# Pure_VCA.net
KiCad netlist of a schematic drawn in EAGLE
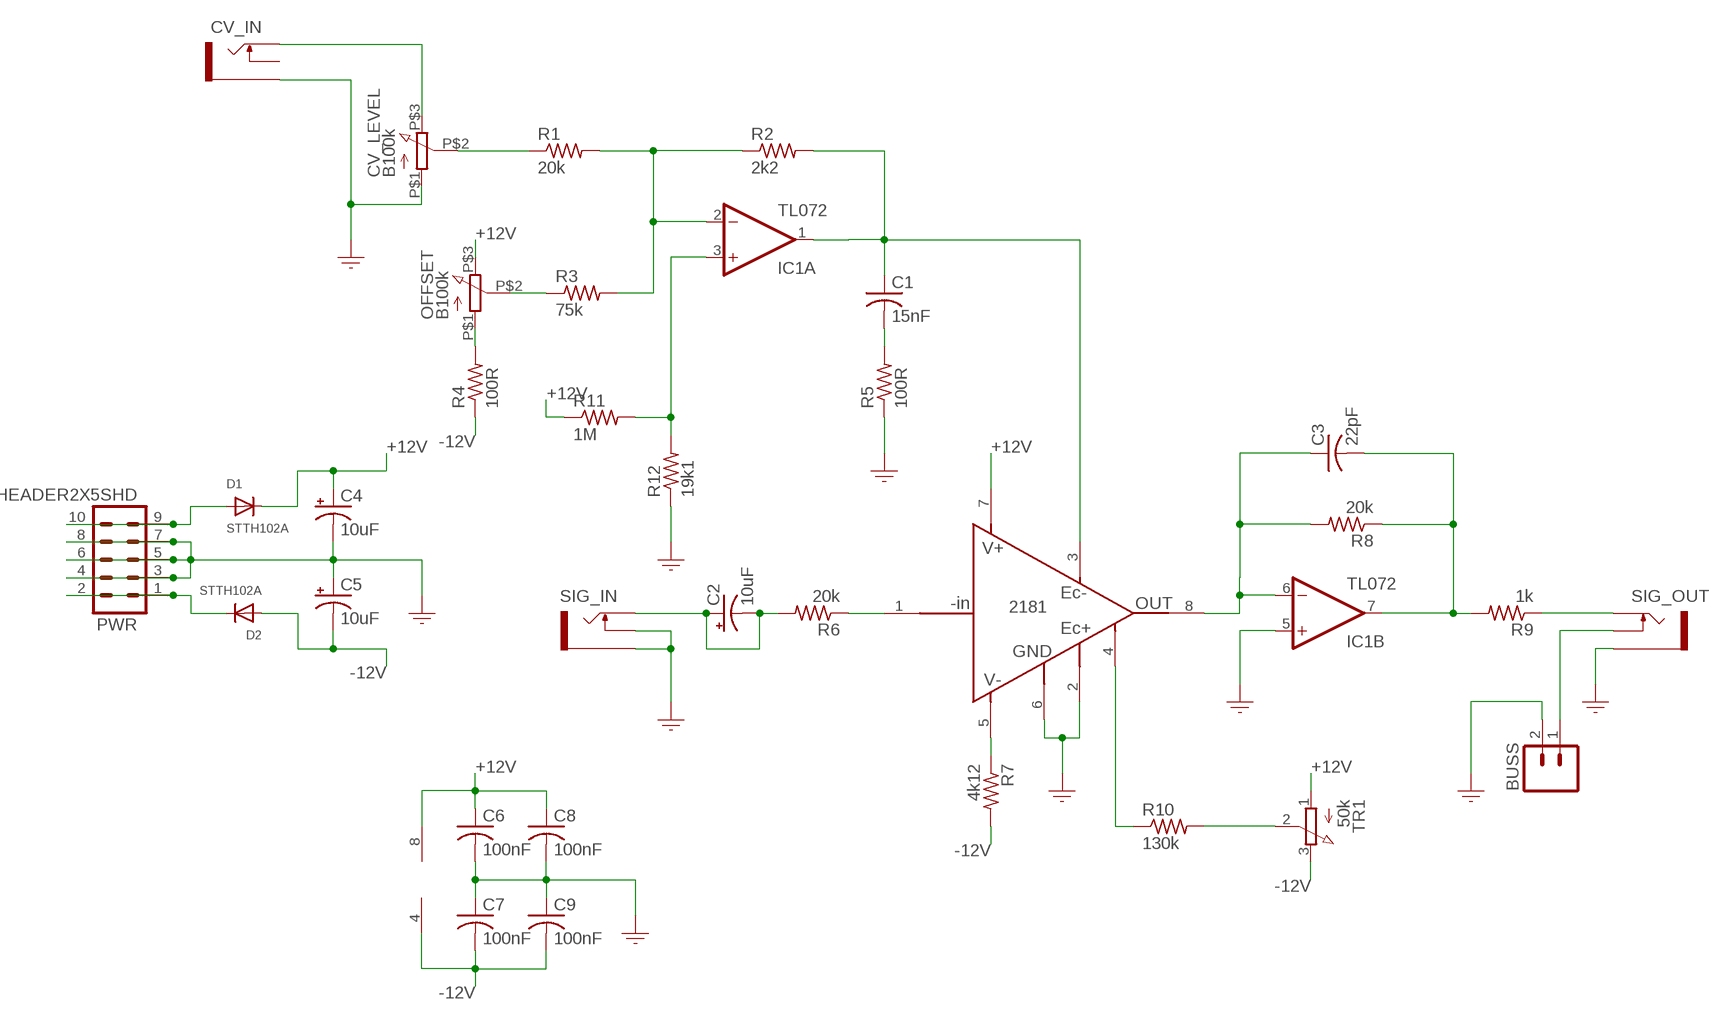
[diagram p0: schematic, sheet 1]

(export (version "E")
  (design (tool "Eeschema 10.0.6"))
  (components
    (comp (ref "BUSS")
      (value "HEADER1X2PTH")
      (footprint "eagle-import:1X02")
      (libsource (lib "eagle-import") (part "HEADER1X2PTH"))
    )
    (comp (ref "C1")
      (value "15nF")
      (footprint "eagle-import:C0805")
      (libsource (lib "eagle-import") (part "CAPACITOR-USC0805"))
    )
    (comp (ref "C2")
      (value "10uF")
      (footprint "eagle-import:153CLV-0505")
      (libsource (lib "eagle-import") (part "CAPACITOR_POL-US153CLV-0505"))
    )
    (comp (ref "C3")
      (value "22pF")
      (footprint "eagle-import:C0805")
      (libsource (lib "eagle-import") (part "CAPACITOR-USC0805"))
    )
    (comp (ref "C4")
      (value "10uF")
      (footprint "eagle-import:153CLV-0505")
      (libsource (lib "eagle-import") (part "CAPACITOR_POL-US153CLV-0505"))
    )
    (comp (ref "C5")
      (value "10uF")
      (footprint "eagle-import:153CLV-0505")
      (libsource (lib "eagle-import") (part "CAPACITOR_POL-US153CLV-0505"))
    )
    (comp (ref "C6")
      (value "100nF")
      (footprint "eagle-import:C0805")
      (libsource (lib "eagle-import") (part "CAPACITOR-USC0805"))
    )
    (comp (ref "C7")
      (value "100nF")
      (footprint "eagle-import:C0805")
      (libsource (lib "eagle-import") (part "CAPACITOR-USC0805"))
    )
    (comp (ref "C8")
      (value "100nF")
      (footprint "eagle-import:C0805")
      (libsource (lib "eagle-import") (part "CAPACITOR-USC0805"))
    )
    (comp (ref "C9")
      (value "100nF")
      (footprint "eagle-import:C0805")
      (libsource (lib "eagle-import") (part "CAPACITOR-USC0805"))
    )
    (comp (ref "CV_IN")
      (value "PJ301M-12")
      (footprint "eagle-import:PJ301M-12")
      (libsource (lib "eagle-import") (part "SOCKET_MONO_3.5MMPJ301M-12"))
    )
    (comp (ref "CV_LEVEL")
      (value "B100k")
      (footprint "eagle-import:POTENTIOMETER_9MM")
      (libsource (lib "eagle-import") (part "RESISTOR_VARIABLE9MM_POT"))
    )
    (comp (ref "D1")
      (value "STTH102A")
      (footprint "eagle-import:SMADIODE")
      (libsource (lib "eagle-import") (part "DIODESMA"))
    )
    (comp (ref "D2")
      (value "STTH102A")
      (footprint "eagle-import:SMADIODE")
      (libsource (lib "eagle-import") (part "DIODESMA"))
    )
    (comp (ref "IC1")
      (value "TL072")
      (footprint "eagle-import:SO08")
      (libsource (lib "eagle-import") (part "OPAMP_DUALD"))
    )
    (comp (ref "IC2")
      (value "THAT2181")
      (footprint "eagle-import:SOIC--8")
      (libsource (lib "eagle-import") (part "VCA_THAT2181"))
    )
    (comp (ref "OFFSET")
      (value "B100k")
      (footprint "eagle-import:POTENTIOMETER_9MM")
      (libsource (lib "eagle-import") (part "RESISTOR_VARIABLE9MM_POT"))
    )
    (comp (ref "PWR")
      (value "HEADER2X5SHD")
      (footprint "eagle-import:2X5-SHROUDED")
      (libsource (lib "eagle-import") (part "HEADER2X5SHD"))
    )
    (comp (ref "R1")
      (value "20k")
      (footprint "eagle-import:R0805")
      (libsource (lib "eagle-import") (part "RESISTOR_USR0805"))
    )
    (comp (ref "R2")
      (value "2k2")
      (footprint "eagle-import:R0805")
      (libsource (lib "eagle-import") (part "RESISTOR_USR0805"))
    )
    (comp (ref "R3")
      (value "75k")
      (footprint "eagle-import:R0805")
      (libsource (lib "eagle-import") (part "RESISTOR_USR0805"))
    )
    (comp (ref "R4")
      (value "100R")
      (footprint "eagle-import:R0805")
      (libsource (lib "eagle-import") (part "RESISTOR_USR0805"))
    )
    (comp (ref "R5")
      (value "100R")
      (footprint "eagle-import:R0805")
      (libsource (lib "eagle-import") (part "RESISTOR_USR0805"))
    )
    (comp (ref "R6")
      (value "20k")
      (footprint "eagle-import:R0805")
      (libsource (lib "eagle-import") (part "RESISTOR_USR0805"))
    )
    (comp (ref "R7")
      (value "4k12")
      (footprint "eagle-import:R0805")
      (libsource (lib "eagle-import") (part "RESISTOR_USR0805"))
    )
    (comp (ref "R8")
      (value "20k")
      (footprint "eagle-import:R0805")
      (libsource (lib "eagle-import") (part "RESISTOR_USR0805"))
    )
    (comp (ref "R9")
      (value "1k")
      (footprint "eagle-import:R0805")
      (libsource (lib "eagle-import") (part "RESISTOR_USR0805"))
    )
    (comp (ref "R10")
      (value "130k")
      (footprint "eagle-import:R0805")
      (libsource (lib "eagle-import") (part "RESISTOR_USR0805"))
    )
    (comp (ref "R11")
      (value "1M")
      (footprint "eagle-import:R0805")
      (libsource (lib "eagle-import") (part "RESISTOR_USR0805"))
    )
    (comp (ref "R12")
      (value "19k1")
      (footprint "eagle-import:R0805")
      (libsource (lib "eagle-import") (part "RESISTOR_USR0805"))
    )
    (comp (ref "SIG_IN")
      (value "PJ301M-12")
      (footprint "eagle-import:PJ301M-12")
      (libsource (lib "eagle-import") (part "SOCKET_MONO_3.5MMPJ301M-12"))
    )
    (comp (ref "SIG_OUT")
      (value "PJ301M-12")
      (footprint "eagle-import:PJ301M-12")
      (libsource (lib "eagle-import") (part "SOCKET_MONO_3.5MMPJ301M-12"))
    )
    (comp (ref "TR1")
      (value "50k")
      (footprint "eagle-import:TRIMMER_TH")
      (libsource (lib "eagle-import") (part "RESISTOR_VARIABLETRIMMER_TH"))
    )
  )
  (nets
    (net (code "1") (name "/+12V") (class "Default")
      (node (ref "C4") (pin "+") (pinfunction "+_+") (pintype "passive"))
      (node (ref "C6") (pin "1") (pinfunction "1_1") (pintype "passive"))
      (node (ref "C8") (pin "1") (pinfunction "1_1") (pintype "passive"))
      (node (ref "D1") (pin "C") (pinfunction "C_C") (pintype "passive"))
      (node (ref "IC1") (pin "8") (pinfunction "V+_8") (pintype "power_in"))
      (node (ref "IC2") (pin "7") (pinfunction "V+_7") (pintype "bidirectional"))
      (node (ref "OFFSET") (pin "P$3") (pinfunction "3_P$3") (pintype "passive"))
      (node (ref "R11") (pin "1") (pinfunction "1_1") (pintype "passive"))
      (node (ref "TR1") (pin "1") (pinfunction "1_1") (pintype "passive"))
    )
    (net (code "2") (name "/-12V") (class "Default")
      (node (ref "C5") (pin "-") (pinfunction "-_-") (pintype "passive"))
      (node (ref "C7") (pin "2") (pinfunction "2_2") (pintype "passive"))
      (node (ref "C9") (pin "2") (pinfunction "2_2") (pintype "passive"))
      (node (ref "D2") (pin "A") (pinfunction "A_A") (pintype "passive"))
      (node (ref "IC1") (pin "4") (pinfunction "V-_4") (pintype "power_in"))
      (node (ref "R4") (pin "1") (pinfunction "1_1") (pintype "passive"))
      (node (ref "R7") (pin "2") (pinfunction "2_2") (pintype "passive"))
      (node (ref "TR1") (pin "3") (pinfunction "3_3") (pintype "passive"))
    )
    (net (code "3") (name "GND") (class "Default")
      (node (ref "BUSS") (pin "2") (pinfunction "2_2") (pintype "passive"))
      (node (ref "C4") (pin "-") (pinfunction "-_-") (pintype "passive"))
      (node (ref "C5") (pin "+") (pinfunction "+_+") (pintype "passive"))
      (node (ref "C6") (pin "2") (pinfunction "2_2") (pintype "passive"))
      (node (ref "C7") (pin "1") (pinfunction "1_1") (pintype "passive"))
      (node (ref "C8") (pin "2") (pinfunction "2_2") (pintype "passive"))
      (node (ref "C9") (pin "1") (pinfunction "1_1") (pintype "passive"))
      (node (ref "CV_IN") (pin "GND") (pinfunction "SLEEVE_GND") (pintype "passive"))
      (node (ref "CV_LEVEL") (pin "P$1") (pinfunction "1_P$1") (pintype "passive"))
      (node (ref "IC1") (pin "5") (pinfunction "+IN_5") (pintype "input"))
      (node (ref "IC2") (pin "2") (pinfunction "EC+_2") (pintype "bidirectional"))
      (node (ref "IC2") (pin "6") (pinfunction "GND_6") (pintype "bidirectional"))
      (node (ref "PWR") (pin "3") (pinfunction "3_3") (pintype "passive"))
      (node (ref "PWR") (pin "4") (pinfunction "4_4") (pintype "passive"))
      (node (ref "PWR") (pin "5") (pinfunction "5_5") (pintype "passive"))
      (node (ref "PWR") (pin "6") (pinfunction "6_6") (pintype "passive"))
      (node (ref "PWR") (pin "7") (pinfunction "7_7") (pintype "passive"))
      (node (ref "PWR") (pin "8") (pinfunction "8_8") (pintype "passive"))
      (node (ref "R12") (pin "1") (pinfunction "1_1") (pintype "passive"))
      (node (ref "R5") (pin "1") (pinfunction "1_1") (pintype "passive"))
      (node (ref "SIG_IN") (pin "GND") (pinfunction "SLEEVE_GND") (pintype "passive"))
      (node (ref "SIG_IN") (pin "NORM") (pinfunction "SWITCH_NORM") (pintype "passive"))
      (node (ref "SIG_OUT") (pin "GND") (pinfunction "SLEEVE_GND") (pintype "passive"))
    )
    (net (code "4") (name "Net-(C1-Pad2)") (class "Default")
      (node (ref "C1") (pin "2") (pinfunction "2_2") (pintype "passive"))
      (node (ref "R5") (pin "2") (pinfunction "2_2") (pintype "passive"))
    )
    (net (code "5") (name "Net-(C2-Pad+)") (class "Default")
      (node (ref "C2") (pin "+") (pinfunction "+_+") (pintype "passive"))
      (node (ref "C2") (pin "-") (pinfunction "-_-") (pintype "passive"))
      (node (ref "R6") (pin "2") (pinfunction "2_2") (pintype "passive"))
      (node (ref "SIG_IN") (pin "TIP") (pinfunction "TIP_TIP") (pintype "passive"))
    )
    (net (code "6") (name "Net-(CV_LEVEL-2)") (class "Default")
      (node (ref "CV_LEVEL") (pin "P$2") (pinfunction "2_P$2") (pintype "passive"))
      (node (ref "R1") (pin "1") (pinfunction "1_1") (pintype "passive"))
    )
    (net (code "7") (name "Net-(CV_LEVEL-3)") (class "Default")
      (node (ref "CV_IN") (pin "TIP") (pinfunction "TIP_TIP") (pintype "passive"))
      (node (ref "CV_LEVEL") (pin "P$3") (pinfunction "3_P$3") (pintype "passive"))
    )
    (net (code "8") (name "Net-(D1-PadA)") (class "Default")
      (node (ref "D1") (pin "A") (pinfunction "A_A") (pintype "passive"))
      (node (ref "PWR") (pin "10") (pinfunction "10_10") (pintype "passive"))
      (node (ref "PWR") (pin "9") (pinfunction "9_9") (pintype "passive"))
    )
    (net (code "9") (name "Net-(D2-PadC)") (class "Default")
      (node (ref "D2") (pin "C") (pinfunction "C_C") (pintype "passive"))
      (node (ref "PWR") (pin "1") (pinfunction "1_1") (pintype "passive"))
      (node (ref "PWR") (pin "2") (pinfunction "2_2") (pintype "passive"))
    )
    (net (code "10") (name "Net-(IC1A-+IN)") (class "Default")
      (node (ref "IC1") (pin "3") (pinfunction "+IN_3") (pintype "input"))
      (node (ref "R11") (pin "2") (pinfunction "2_2") (pintype "passive"))
      (node (ref "R12") (pin "2") (pinfunction "2_2") (pintype "passive"))
    )
    (net (code "11") (name "Net-(IC1A--IN)") (class "Default")
      (node (ref "IC1") (pin "2") (pinfunction "-IN_2") (pintype "input"))
      (node (ref "R1") (pin "2") (pinfunction "2_2") (pintype "passive"))
      (node (ref "R2") (pin "1") (pinfunction "1_1") (pintype "passive"))
      (node (ref "R3") (pin "2") (pinfunction "2_2") (pintype "passive"))
    )
    (net (code "12") (name "Net-(IC1A-OUT)") (class "Default")
      (node (ref "C1") (pin "1") (pinfunction "1_1") (pintype "passive"))
      (node (ref "IC1") (pin "1") (pinfunction "OUT_1") (pintype "output"))
      (node (ref "IC2") (pin "3") (pinfunction "EC-_3") (pintype "bidirectional"))
      (node (ref "R2") (pin "2") (pinfunction "2_2") (pintype "passive"))
    )
    (net (code "13") (name "Net-(IC1B--IN)") (class "Default")
      (node (ref "C3") (pin "1") (pinfunction "1_1") (pintype "passive"))
      (node (ref "IC1") (pin "6") (pinfunction "-IN_6") (pintype "input"))
      (node (ref "IC2") (pin "8") (pinfunction "OUT_8") (pintype "bidirectional"))
      (node (ref "R8") (pin "2") (pinfunction "2_2") (pintype "passive"))
    )
    (net (code "14") (name "Net-(IC1B-OUT)") (class "Default")
      (node (ref "C3") (pin "2") (pinfunction "2_2") (pintype "passive"))
      (node (ref "IC1") (pin "7") (pinfunction "OUT_7") (pintype "output"))
      (node (ref "R8") (pin "1") (pinfunction "1_1") (pintype "passive"))
      (node (ref "R9") (pin "2") (pinfunction "2_2") (pintype "passive"))
    )
    (net (code "15") (name "Net-(IC2--IN)") (class "Default")
      (node (ref "IC2") (pin "1") (pinfunction "-IN_1") (pintype "bidirectional"))
      (node (ref "R6") (pin "1") (pinfunction "1_1") (pintype "passive"))
    )
    (net (code "16") (name "Net-(IC2-SYM)") (class "Default")
      (node (ref "IC2") (pin "4") (pinfunction "SYM_4") (pintype "bidirectional"))
      (node (ref "R10") (pin "1") (pinfunction "1_1") (pintype "passive"))
    )
    (net (code "17") (name "Net-(IC2-V-)") (class "Default")
      (node (ref "IC2") (pin "5") (pinfunction "V-_5") (pintype "bidirectional"))
      (node (ref "R7") (pin "1") (pinfunction "1_1") (pintype "passive"))
    )
    (net (code "18") (name "Net-(OFFSET-1)") (class "Default")
      (node (ref "OFFSET") (pin "P$1") (pinfunction "1_P$1") (pintype "passive"))
      (node (ref "R4") (pin "2") (pinfunction "2_2") (pintype "passive"))
    )
    (net (code "19") (name "Net-(OFFSET-2)") (class "Default")
      (node (ref "OFFSET") (pin "P$2") (pinfunction "2_P$2") (pintype "passive"))
      (node (ref "R3") (pin "1") (pinfunction "1_1") (pintype "passive"))
    )
    (net (code "20") (name "Net-(R9-Pad1)") (class "Default")
      (node (ref "R9") (pin "1") (pinfunction "1_1") (pintype "passive"))
      (node (ref "SIG_OUT") (pin "TIP") (pinfunction "TIP_TIP") (pintype "passive"))
    )
    (net (code "21") (name "Net-(R10-Pad2)") (class "Default")
      (node (ref "R10") (pin "2") (pinfunction "2_2") (pintype "passive"))
      (node (ref "TR1") (pin "2") (pinfunction "2_2") (pintype "passive"))
    )
    (net (code "22") (name "Net-(SIG_OUT-SWITCH)") (class "Default")
      (node (ref "BUSS") (pin "1") (pinfunction "1_1") (pintype "passive"))
      (node (ref "SIG_OUT") (pin "NORM") (pinfunction "SWITCH_NORM") (pintype "passive"))
    )
    (net (code "23") (name "unconnected-(CV_IN-SWITCH-PadNORM)") (class "Default")
      (node (ref "CV_IN") (pin "NORM") (pinfunction "SWITCH_NORM") (pintype "passive"))
    )
  )
)
